# k26_baseboard_cameras.net
KiCad netlist of a schematic drawn in Altium Designer
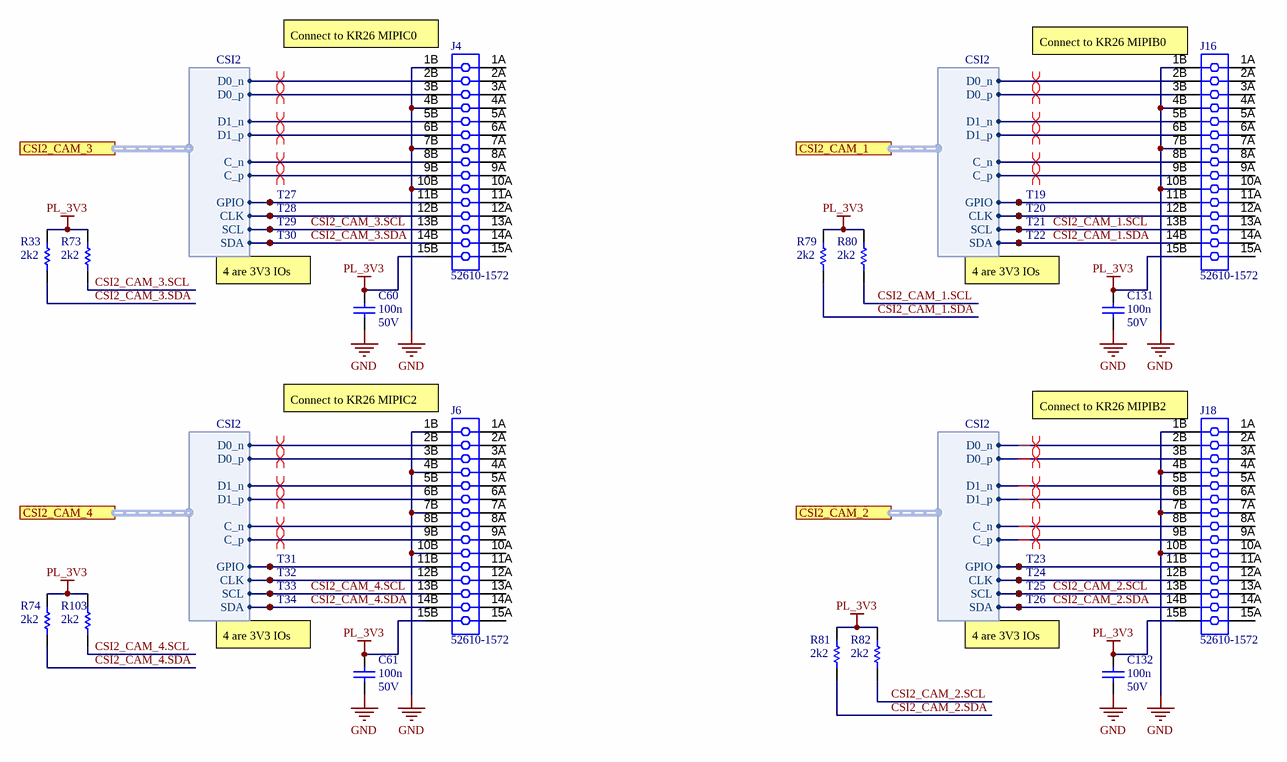
[diagram p0: k26_baseboard_cameras.SchDoc]

(export (version "E")
  (design (tool "Eeschema 10.0.6"))
  (components
    (comp (ref "C60")
      (value "100n")
      (footprint "k26_FPGA_drone_baseboard:CAPC0402")
      (fields
        (field (name "MANUFACTURER") "Yageo")
        (field (name "MANUFACTURER PART NUMBER") "CC0402KRX5R9BB104")
        (field (name "RATED DC VOLTAGE (URDC)") "50V")
      )
      (libsource (lib "k26_FPGA_drone_baseboard") (part "cap0402"))
    )
    (comp (ref "C61")
      (value "100n")
      (footprint "k26_FPGA_drone_baseboard:CAPC0402")
      (fields
        (field (name "MANUFACTURER") "Yageo")
        (field (name "MANUFACTURER PART NUMBER") "CC0402KRX5R9BB104")
        (field (name "RATED DC VOLTAGE (URDC)") "50V")
      )
      (libsource (lib "k26_FPGA_drone_baseboard") (part "cap0402"))
    )
    (comp (ref "C131")
      (value "100n")
      (footprint "k26_FPGA_drone_baseboard:CAPC0402")
      (fields
        (field (name "MANUFACTURER") "Yageo")
        (field (name "MANUFACTURER PART NUMBER") "CC0402KRX5R9BB104")
        (field (name "RATED DC VOLTAGE (URDC)") "50V")
      )
      (libsource (lib "k26_FPGA_drone_baseboard") (part "cap0402"))
    )
    (comp (ref "C132")
      (value "100n")
      (footprint "k26_FPGA_drone_baseboard:CAPC0402")
      (fields
        (field (name "MANUFACTURER") "Yageo")
        (field (name "MANUFACTURER PART NUMBER") "CC0402KRX5R9BB104")
        (field (name "RATED DC VOLTAGE (URDC)") "50V")
      )
      (libsource (lib "k26_FPGA_drone_baseboard") (part "cap0402"))
    )
    (comp (ref "J4")
      (value "52610-1572")
      (footprint "MOLX-52610-1572")
      (fields (field (name "MANUFACTURER") "Molex"))
      (libsource (lib "k26_FPGA_drone_baseboard") (part "MOLX-52610-1572"))
    )
    (comp (ref "J6")
      (value "52610-1572")
      (footprint "MOLX-52610-1572")
      (fields (field (name "MANUFACTURER") "Molex"))
      (libsource (lib "k26_FPGA_drone_baseboard") (part "MOLX-52610-1572"))
    )
    (comp (ref "J16")
      (value "52610-1572")
      (footprint "MOLX-52610-1572")
      (fields (field (name "MANUFACTURER") "Molex"))
      (libsource (lib "k26_FPGA_drone_baseboard") (part "MOLX-52610-1572"))
    )
    (comp (ref "J18")
      (value "52610-1572")
      (footprint "MOLX-52610-1572")
      (fields (field (name "MANUFACTURER") "Molex"))
      (libsource (lib "k26_FPGA_drone_baseboard") (part "MOLX-52610-1572"))
    )
    (comp (ref "R33")
      (value "2k2")
      (footprint "k26_FPGA_drone_baseboard:RES0402")
      (fields
        (field (name "MANUFACTURER") "Vishay")
        (field (name "MANUFACTURER PART NUMBER") "CRCW04022K20FKED")
        (field (name "TOLERANCE") "1%")
      )
      (libsource (lib "k26_FPGA_drone_baseboard") (part "res0402"))
    )
    (comp (ref "R73")
      (value "2k2")
      (footprint "k26_FPGA_drone_baseboard:RES0402")
      (fields
        (field (name "MANUFACTURER") "Vishay")
        (field (name "MANUFACTURER PART NUMBER") "CRCW04022K20FKED")
        (field (name "TOLERANCE") "1%")
      )
      (libsource (lib "k26_FPGA_drone_baseboard") (part "res0402"))
    )
    (comp (ref "R74")
      (value "2k2")
      (footprint "k26_FPGA_drone_baseboard:RES0402")
      (fields
        (field (name "MANUFACTURER") "Vishay")
        (field (name "MANUFACTURER PART NUMBER") "CRCW04022K20FKED")
        (field (name "TOLERANCE") "1%")
      )
      (libsource (lib "k26_FPGA_drone_baseboard") (part "res0402"))
    )
    (comp (ref "R79")
      (value "2k2")
      (footprint "k26_FPGA_drone_baseboard:RES0402")
      (fields
        (field (name "MANUFACTURER") "Vishay")
        (field (name "MANUFACTURER PART NUMBER") "CRCW04022K20FKED")
        (field (name "TOLERANCE") "1%")
      )
      (libsource (lib "k26_FPGA_drone_baseboard") (part "res0402"))
    )
    (comp (ref "R80")
      (value "2k2")
      (footprint "k26_FPGA_drone_baseboard:RES0402")
      (fields
        (field (name "MANUFACTURER") "Vishay")
        (field (name "MANUFACTURER PART NUMBER") "CRCW04022K20FKED")
        (field (name "TOLERANCE") "1%")
      )
      (libsource (lib "k26_FPGA_drone_baseboard") (part "res0402"))
    )
    (comp (ref "R81")
      (value "2k2")
      (footprint "k26_FPGA_drone_baseboard:RES0402")
      (fields
        (field (name "MANUFACTURER") "Vishay")
        (field (name "MANUFACTURER PART NUMBER") "CRCW04022K20FKED")
        (field (name "TOLERANCE") "1%")
      )
      (libsource (lib "k26_FPGA_drone_baseboard") (part "res0402"))
    )
    (comp (ref "R82")
      (value "2k2")
      (footprint "k26_FPGA_drone_baseboard:RES0402")
      (fields
        (field (name "MANUFACTURER") "Vishay")
        (field (name "MANUFACTURER PART NUMBER") "CRCW04022K20FKED")
        (field (name "TOLERANCE") "1%")
      )
      (libsource (lib "k26_FPGA_drone_baseboard") (part "res0402"))
    )
    (comp (ref "R103")
      (value "2k2")
      (footprint "k26_FPGA_drone_baseboard:RES0402")
      (fields
        (field (name "MANUFACTURER") "Vishay")
        (field (name "MANUFACTURER PART NUMBER") "CRCW04022K20FKED")
        (field (name "TOLERANCE") "1%")
      )
      (libsource (lib "k26_FPGA_drone_baseboard") (part "res0402"))
    )
    (comp (ref "T19")
      (value "CMP-01283-1")
      (footprint "Pad-1mm")
      (description "1mm SMT Test Pad")
      (libsource (lib "k26_FPGA_drone_baseboard") (part "CMP-01283-1"))
    )
    (comp (ref "T20")
      (value "CMP-01283-1")
      (footprint "Pad-1mm")
      (description "1mm SMT Test Pad")
      (libsource (lib "k26_FPGA_drone_baseboard") (part "CMP-01283-1"))
    )
    (comp (ref "T21")
      (value "CMP-01283-1")
      (footprint "Pad-1mm")
      (description "1mm SMT Test Pad")
      (libsource (lib "k26_FPGA_drone_baseboard") (part "CMP-01283-1"))
    )
    (comp (ref "T22")
      (value "CMP-01283-1")
      (footprint "Pad-1mm")
      (description "1mm SMT Test Pad")
      (libsource (lib "k26_FPGA_drone_baseboard") (part "CMP-01283-1"))
    )
    (comp (ref "T23")
      (value "CMP-01283-1")
      (footprint "Pad-1mm")
      (description "1mm SMT Test Pad")
      (libsource (lib "k26_FPGA_drone_baseboard") (part "CMP-01283-1"))
    )
    (comp (ref "T24")
      (value "CMP-01283-1")
      (footprint "Pad-1mm")
      (description "1mm SMT Test Pad")
      (libsource (lib "k26_FPGA_drone_baseboard") (part "CMP-01283-1"))
    )
    (comp (ref "T25")
      (value "CMP-01283-1")
      (footprint "Pad-1mm")
      (description "1mm SMT Test Pad")
      (libsource (lib "k26_FPGA_drone_baseboard") (part "CMP-01283-1"))
    )
    (comp (ref "T26")
      (value "CMP-01283-1")
      (footprint "Pad-1mm")
      (description "1mm SMT Test Pad")
      (libsource (lib "k26_FPGA_drone_baseboard") (part "CMP-01283-1"))
    )
    (comp (ref "T27")
      (value "CMP-01283-1")
      (footprint "Pad-1mm")
      (description "1mm SMT Test Pad")
      (libsource (lib "k26_FPGA_drone_baseboard") (part "CMP-01283-1"))
    )
    (comp (ref "T28")
      (value "CMP-01283-1")
      (footprint "Pad-1mm")
      (description "1mm SMT Test Pad")
      (libsource (lib "k26_FPGA_drone_baseboard") (part "CMP-01283-1"))
    )
    (comp (ref "T29")
      (value "CMP-01283-1")
      (footprint "Pad-1mm")
      (description "1mm SMT Test Pad")
      (libsource (lib "k26_FPGA_drone_baseboard") (part "CMP-01283-1"))
    )
    (comp (ref "T30")
      (value "CMP-01283-1")
      (footprint "Pad-1mm")
      (description "1mm SMT Test Pad")
      (libsource (lib "k26_FPGA_drone_baseboard") (part "CMP-01283-1"))
    )
    (comp (ref "T31")
      (value "CMP-01283-1")
      (footprint "Pad-1mm")
      (description "1mm SMT Test Pad")
      (libsource (lib "k26_FPGA_drone_baseboard") (part "CMP-01283-1"))
    )
    (comp (ref "T32")
      (value "CMP-01283-1")
      (footprint "Pad-1mm")
      (description "1mm SMT Test Pad")
      (libsource (lib "k26_FPGA_drone_baseboard") (part "CMP-01283-1"))
    )
    (comp (ref "T33")
      (value "CMP-01283-1")
      (footprint "Pad-1mm")
      (description "1mm SMT Test Pad")
      (libsource (lib "k26_FPGA_drone_baseboard") (part "CMP-01283-1"))
    )
    (comp (ref "T34")
      (value "CMP-01283-1")
      (footprint "Pad-1mm")
      (description "1mm SMT Test Pad")
      (libsource (lib "k26_FPGA_drone_baseboard") (part "CMP-01283-1"))
    )
  )
  (nets
    (net (code "2") (name "/CSI2_CAM_1.SCL") (class "Default")
      (node (ref "J16") (pin "13B") (pinfunction "13B_13B") (pintype "passive"))
      (node (ref "R80") (pin "1") (pinfunction "1_1") (pintype "passive"))
      (node (ref "T21") (pin "1") (pinfunction "1_1") (pintype "passive"))
    )
    (net (code "3") (name "/CSI2_CAM_1.SDA") (class "Default")
      (node (ref "J16") (pin "14B") (pinfunction "14B_14B") (pintype "passive"))
      (node (ref "R79") (pin "1") (pinfunction "1_1") (pintype "passive"))
      (node (ref "T22") (pin "1") (pinfunction "1_1") (pintype "passive"))
    )
    (net (code "4") (name "/CSI2_CAM_2.SCL") (class "Default")
      (node (ref "J18") (pin "13B") (pinfunction "13B_13B") (pintype "passive"))
      (node (ref "R82") (pin "1") (pinfunction "1_1") (pintype "passive"))
      (node (ref "T25") (pin "1") (pinfunction "1_1") (pintype "passive"))
    )
    (net (code "5") (name "/CSI2_CAM_2.SDA") (class "Default")
      (node (ref "J18") (pin "14B") (pinfunction "14B_14B") (pintype "passive"))
      (node (ref "R81") (pin "1") (pinfunction "1_1") (pintype "passive"))
      (node (ref "T26") (pin "1") (pinfunction "1_1") (pintype "passive"))
    )
    (net (code "6") (name "/CSI2_CAM_3.SCL") (class "Default")
      (node (ref "J4") (pin "13B") (pinfunction "13B_13B") (pintype "passive"))
      (node (ref "R73") (pin "1") (pinfunction "1_1") (pintype "passive"))
      (node (ref "T29") (pin "1") (pinfunction "1_1") (pintype "passive"))
    )
    (net (code "7") (name "/CSI2_CAM_3.SDA") (class "Default")
      (node (ref "J4") (pin "14B") (pinfunction "14B_14B") (pintype "passive"))
      (node (ref "R33") (pin "1") (pinfunction "1_1") (pintype "passive"))
      (node (ref "T30") (pin "1") (pinfunction "1_1") (pintype "passive"))
    )
    (net (code "8") (name "/CSI2_CAM_4.SCL") (class "Default")
      (node (ref "J6") (pin "13B") (pinfunction "13B_13B") (pintype "passive"))
      (node (ref "R103") (pin "1") (pinfunction "1_1") (pintype "passive"))
      (node (ref "T33") (pin "1") (pinfunction "1_1") (pintype "passive"))
    )
    (net (code "9") (name "/CSI2_CAM_4.SDA") (class "Default")
      (node (ref "J6") (pin "14B") (pinfunction "14B_14B") (pintype "passive"))
      (node (ref "R74") (pin "1") (pinfunction "1_1") (pintype "passive"))
      (node (ref "T34") (pin "1") (pinfunction "1_1") (pintype "passive"))
    )
    (net (code "11") (name "GND") (class "Default")
      (node (ref "C131") (pin "1") (pinfunction "1_1") (pintype "passive"))
      (node (ref "C132") (pin "1") (pinfunction "1_1") (pintype "passive"))
      (node (ref "C60") (pin "1") (pinfunction "1_1") (pintype "passive"))
      (node (ref "C61") (pin "1") (pinfunction "1_1") (pintype "passive"))
      (node (ref "J16") (pin "10B") (pinfunction "10B_10B") (pintype "passive"))
      (node (ref "J16") (pin "1B") (pinfunction "1B_1B") (pintype "passive"))
      (node (ref "J16") (pin "4B") (pinfunction "4B_4B") (pintype "passive"))
      (node (ref "J16") (pin "7B") (pinfunction "7B_7B") (pintype "passive"))
      (node (ref "J18") (pin "10B") (pinfunction "10B_10B") (pintype "passive"))
      (node (ref "J18") (pin "1B") (pinfunction "1B_1B") (pintype "passive"))
      (node (ref "J18") (pin "4B") (pinfunction "4B_4B") (pintype "passive"))
      (node (ref "J18") (pin "7B") (pinfunction "7B_7B") (pintype "passive"))
      (node (ref "J4") (pin "10B") (pinfunction "10B_10B") (pintype "passive"))
      (node (ref "J4") (pin "1B") (pinfunction "1B_1B") (pintype "passive"))
      (node (ref "J4") (pin "4B") (pinfunction "4B_4B") (pintype "passive"))
      (node (ref "J4") (pin "7B") (pinfunction "7B_7B") (pintype "passive"))
      (node (ref "J6") (pin "10B") (pinfunction "10B_10B") (pintype "passive"))
      (node (ref "J6") (pin "1B") (pinfunction "1B_1B") (pintype "passive"))
      (node (ref "J6") (pin "4B") (pinfunction "4B_4B") (pintype "passive"))
      (node (ref "J6") (pin "7B") (pinfunction "7B_7B") (pintype "passive"))
    )
    (net (code "12") (name "Net-(J4-Pad11B)") (class "Default")
      (node (ref "J4") (pin "11B") (pinfunction "11B_11B") (pintype "passive"))
      (node (ref "T27") (pin "1") (pinfunction "1_1") (pintype "passive"))
    )
    (net (code "13") (name "Net-(J4-Pad12B)") (class "Default")
      (node (ref "J4") (pin "12B") (pinfunction "12B_12B") (pintype "passive"))
      (node (ref "T28") (pin "1") (pinfunction "1_1") (pintype "passive"))
    )
    (net (code "14") (name "Net-(J6-Pad11B)") (class "Default")
      (node (ref "J6") (pin "11B") (pinfunction "11B_11B") (pintype "passive"))
      (node (ref "T31") (pin "1") (pinfunction "1_1") (pintype "passive"))
    )
    (net (code "15") (name "Net-(J6-Pad12B)") (class "Default")
      (node (ref "J6") (pin "12B") (pinfunction "12B_12B") (pintype "passive"))
      (node (ref "T32") (pin "1") (pinfunction "1_1") (pintype "passive"))
    )
    (net (code "16") (name "Net-(J16-Pad11B)") (class "Default")
      (node (ref "J16") (pin "11B") (pinfunction "11B_11B") (pintype "passive"))
      (node (ref "T19") (pin "1") (pinfunction "1_1") (pintype "passive"))
    )
    (net (code "17") (name "Net-(J16-Pad12B)") (class "Default")
      (node (ref "J16") (pin "12B") (pinfunction "12B_12B") (pintype "passive"))
      (node (ref "T20") (pin "1") (pinfunction "1_1") (pintype "passive"))
    )
    (net (code "18") (name "Net-(J18-Pad11B)") (class "Default")
      (node (ref "J18") (pin "11B") (pinfunction "11B_11B") (pintype "passive"))
      (node (ref "T23") (pin "1") (pinfunction "1_1") (pintype "passive"))
    )
    (net (code "19") (name "Net-(J18-Pad12B)") (class "Default")
      (node (ref "J18") (pin "12B") (pinfunction "12B_12B") (pintype "passive"))
      (node (ref "T24") (pin "1") (pinfunction "1_1") (pintype "passive"))
    )
    (net (code "20") (name "PL_3V3") (class "Default")
      (node (ref "C131") (pin "2") (pinfunction "2_2") (pintype "passive"))
      (node (ref "C132") (pin "2") (pinfunction "2_2") (pintype "passive"))
      (node (ref "C60") (pin "2") (pinfunction "2_2") (pintype "passive"))
      (node (ref "C61") (pin "2") (pinfunction "2_2") (pintype "passive"))
      (node (ref "J16") (pin "15B") (pinfunction "15B_15B") (pintype "passive"))
      (node (ref "J18") (pin "15B") (pinfunction "15B_15B") (pintype "passive"))
      (node (ref "J4") (pin "15B") (pinfunction "15B_15B") (pintype "passive"))
      (node (ref "J6") (pin "15B") (pinfunction "15B_15B") (pintype "passive"))
      (node (ref "R103") (pin "2") (pinfunction "2_2") (pintype "passive"))
      (node (ref "R33") (pin "2") (pinfunction "2_2") (pintype "passive"))
      (node (ref "R73") (pin "2") (pinfunction "2_2") (pintype "passive"))
      (node (ref "R74") (pin "2") (pinfunction "2_2") (pintype "passive"))
      (node (ref "R79") (pin "2") (pinfunction "2_2") (pintype "passive"))
      (node (ref "R80") (pin "2") (pinfunction "2_2") (pintype "passive"))
      (node (ref "R81") (pin "2") (pinfunction "2_2") (pintype "passive"))
      (node (ref "R82") (pin "2") (pinfunction "2_2") (pintype "passive"))
    )
    (net (code "21") (name "unconnected-(J4-Pad1A)") (class "Default")
      (node (ref "J4") (pin "1A") (pinfunction "1A_1A") (pintype "passive"))
    )
    (net (code "22") (name "unconnected-(J4-Pad2A)") (class "Default")
      (node (ref "J4") (pin "2A") (pinfunction "2A_2A") (pintype "passive"))
    )
    (net (code "23") (name "unconnected-(J4-Pad2B)") (class "Default")
      (node (ref "J4") (pin "2B") (pinfunction "2B_2B") (pintype "passive"))
    )
    (net (code "24") (name "unconnected-(J4-Pad3A)") (class "Default")
      (node (ref "J4") (pin "3A") (pinfunction "3A_3A") (pintype "passive"))
    )
    (net (code "25") (name "unconnected-(J4-Pad3B)") (class "Default")
      (node (ref "J4") (pin "3B") (pinfunction "3B_3B") (pintype "passive"))
    )
    (net (code "26") (name "unconnected-(J4-Pad4A)") (class "Default")
      (node (ref "J4") (pin "4A") (pinfunction "4A_4A") (pintype "passive"))
    )
    (net (code "27") (name "unconnected-(J4-Pad5A)") (class "Default")
      (node (ref "J4") (pin "5A") (pinfunction "5A_5A") (pintype "passive"))
    )
    (net (code "28") (name "unconnected-(J4-Pad5B)") (class "Default")
      (node (ref "J4") (pin "5B") (pinfunction "5B_5B") (pintype "passive"))
    )
    (net (code "29") (name "unconnected-(J4-Pad6A)") (class "Default")
      (node (ref "J4") (pin "6A") (pinfunction "6A_6A") (pintype "passive"))
    )
    (net (code "30") (name "unconnected-(J4-Pad6B)") (class "Default")
      (node (ref "J4") (pin "6B") (pinfunction "6B_6B") (pintype "passive"))
    )
    (net (code "31") (name "unconnected-(J4-Pad7A)") (class "Default")
      (node (ref "J4") (pin "7A") (pinfunction "7A_7A") (pintype "passive"))
    )
    (net (code "32") (name "unconnected-(J4-Pad8A)") (class "Default")
      (node (ref "J4") (pin "8A") (pinfunction "8A_8A") (pintype "passive"))
    )
    (net (code "33") (name "unconnected-(J4-Pad8B)") (class "Default")
      (node (ref "J4") (pin "8B") (pinfunction "8B_8B") (pintype "passive"))
    )
    (net (code "34") (name "unconnected-(J4-Pad9A)") (class "Default")
      (node (ref "J4") (pin "9A") (pinfunction "9A_9A") (pintype "passive"))
    )
    (net (code "35") (name "unconnected-(J4-Pad9B)") (class "Default")
      (node (ref "J4") (pin "9B") (pinfunction "9B_9B") (pintype "passive"))
    )
    (net (code "36") (name "unconnected-(J4-Pad10A)") (class "Default")
      (node (ref "J4") (pin "10A") (pinfunction "10A_10A") (pintype "passive"))
    )
    (net (code "37") (name "unconnected-(J4-Pad11A)") (class "Default")
      (node (ref "J4") (pin "11A") (pinfunction "11A_11A") (pintype "passive"))
    )
    (net (code "38") (name "unconnected-(J4-Pad12A)") (class "Default")
      (node (ref "J4") (pin "12A") (pinfunction "12A_12A") (pintype "passive"))
    )
    (net (code "39") (name "unconnected-(J4-Pad13A)") (class "Default")
      (node (ref "J4") (pin "13A") (pinfunction "13A_13A") (pintype "passive"))
    )
    (net (code "40") (name "unconnected-(J4-Pad14A)") (class "Default")
      (node (ref "J4") (pin "14A") (pinfunction "14A_14A") (pintype "passive"))
    )
    (net (code "41") (name "unconnected-(J4-Pad15A)") (class "Default")
      (node (ref "J4") (pin "15A") (pinfunction "15A_15A") (pintype "passive"))
    )
    (net (code "42") (name "unconnected-(J6-Pad1A)") (class "Default")
      (node (ref "J6") (pin "1A") (pinfunction "1A_1A") (pintype "passive"))
    )
    (net (code "43") (name "unconnected-(J6-Pad2A)") (class "Default")
      (node (ref "J6") (pin "2A") (pinfunction "2A_2A") (pintype "passive"))
    )
    (net (code "44") (name "unconnected-(J6-Pad2B)") (class "Default")
      (node (ref "J6") (pin "2B") (pinfunction "2B_2B") (pintype "passive"))
    )
    (net (code "45") (name "unconnected-(J6-Pad3A)") (class "Default")
      (node (ref "J6") (pin "3A") (pinfunction "3A_3A") (pintype "passive"))
    )
    (net (code "46") (name "unconnected-(J6-Pad3B)") (class "Default")
      (node (ref "J6") (pin "3B") (pinfunction "3B_3B") (pintype "passive"))
    )
    (net (code "47") (name "unconnected-(J6-Pad4A)") (class "Default")
      (node (ref "J6") (pin "4A") (pinfunction "4A_4A") (pintype "passive"))
    )
    (net (code "48") (name "unconnected-(J6-Pad5A)") (class "Default")
      (node (ref "J6") (pin "5A") (pinfunction "5A_5A") (pintype "passive"))
    )
    (net (code "49") (name "unconnected-(J6-Pad5B)") (class "Default")
      (node (ref "J6") (pin "5B") (pinfunction "5B_5B") (pintype "passive"))
    )
    (net (code "50") (name "unconnected-(J6-Pad6A)") (class "Default")
      (node (ref "J6") (pin "6A") (pinfunction "6A_6A") (pintype "passive"))
    )
    (net (code "51") (name "unconnected-(J6-Pad6B)") (class "Default")
      (node (ref "J6") (pin "6B") (pinfunction "6B_6B") (pintype "passive"))
    )
    (net (code "52") (name "unconnected-(J6-Pad7A)") (class "Default")
      (node (ref "J6") (pin "7A") (pinfunction "7A_7A") (pintype "passive"))
    )
    (net (code "53") (name "unconnected-(J6-Pad8A)") (class "Default")
      (node (ref "J6") (pin "8A") (pinfunction "8A_8A") (pintype "passive"))
    )
    (net (code "54") (name "unconnected-(J6-Pad8B)") (class "Default")
      (node (ref "J6") (pin "8B") (pinfunction "8B_8B") (pintype "passive"))
    )
    (net (code "55") (name "unconnected-(J6-Pad9A)") (class "Default")
      (node (ref "J6") (pin "9A") (pinfunction "9A_9A") (pintype "passive"))
    )
    (net (code "56") (name "unconnected-(J6-Pad9B)") (class "Default")
      (node (ref "J6") (pin "9B") (pinfunction "9B_9B") (pintype "passive"))
    )
    (net (code "57") (name "unconnected-(J6-Pad10A)") (class "Default")
      (node (ref "J6") (pin "10A") (pinfunction "10A_10A") (pintype "passive"))
    )
    (net (code "58") (name "unconnected-(J6-Pad11A)") (class "Default")
      (node (ref "J6") (pin "11A") (pinfunction "11A_11A") (pintype "passive"))
    )
    (net (code "59") (name "unconnected-(J6-Pad12A)") (class "Default")
      (node (ref "J6") (pin "12A") (pinfunction "12A_12A") (pintype "passive"))
    )
    (net (code "60") (name "unconnected-(J6-Pad13A)") (class "Default")
      (node (ref "J6") (pin "13A") (pinfunction "13A_13A") (pintype "passive"))
    )
    (net (code "61") (name "unconnected-(J6-Pad14A)") (class "Default")
      (node (ref "J6") (pin "14A") (pinfunction "14A_14A") (pintype "passive"))
    )
    (net (code "62") (name "unconnected-(J6-Pad15A)") (class "Default")
      (node (ref "J6") (pin "15A") (pinfunction "15A_15A") (pintype "passive"))
    )
    (net (code "63") (name "unconnected-(J16-Pad1A)") (class "Default")
      (node (ref "J16") (pin "1A") (pinfunction "1A_1A") (pintype "passive"))
    )
    (net (code "64") (name "unconnected-(J16-Pad2A)") (class "Default")
      (node (ref "J16") (pin "2A") (pinfunction "2A_2A") (pintype "passive"))
    )
    (net (code "65") (name "unconnected-(J16-Pad2B)") (class "Default")
      (node (ref "J16") (pin "2B") (pinfunction "2B_2B") (pintype "passive"))
    )
    (net (code "66") (name "unconnected-(J16-Pad3A)") (class "Default")
      (node (ref "J16") (pin "3A") (pinfunction "3A_3A") (pintype "passive"))
    )
    (net (code "67") (name "unconnected-(J16-Pad3B)") (class "Default")
      (node (ref "J16") (pin "3B") (pinfunction "3B_3B") (pintype "passive"))
    )
    (net (code "68") (name "unconnected-(J16-Pad4A)") (class "Default")
      (node (ref "J16") (pin "4A") (pinfunction "4A_4A") (pintype "passive"))
    )
    (net (code "69") (name "unconnected-(J16-Pad5A)") (class "Default")
      (node (ref "J16") (pin "5A") (pinfunction "5A_5A") (pintype "passive"))
    )
    (net (code "70") (name "unconnected-(J16-Pad5B)") (class "Default")
      (node (ref "J16") (pin "5B") (pinfunction "5B_5B") (pintype "passive"))
    )
    (net (code "71") (name "unconnected-(J16-Pad6A)") (class "Default")
      (node (ref "J16") (pin "6A") (pinfunction "6A_6A") (pintype "passive"))
    )
    (net (code "72") (name "unconnected-(J16-Pad6B)") (class "Default")
      (node (ref "J16") (pin "6B") (pinfunction "6B_6B") (pintype "passive"))
    )
    (net (code "73") (name "unconnected-(J16-Pad7A)") (class "Default")
      (node (ref "J16") (pin "7A") (pinfunction "7A_7A") (pintype "passive"))
    )
    (net (code "74") (name "unconnected-(J16-Pad8A)") (class "Default")
      (node (ref "J16") (pin "8A") (pinfunction "8A_8A") (pintype "passive"))
    )
    (net (code "75") (name "unconnected-(J16-Pad8B)") (class "Default")
      (node (ref "J16") (pin "8B") (pinfunction "8B_8B") (pintype "passive"))
    )
    (net (code "76") (name "unconnected-(J16-Pad9A)") (class "Default")
      (node (ref "J16") (pin "9A") (pinfunction "9A_9A") (pintype "passive"))
    )
    (net (code "77") (name "unconnected-(J16-Pad9B)") (class "Default")
      (node (ref "J16") (pin "9B") (pinfunction "9B_9B") (pintype "passive"))
    )
    (net (code "78") (name "unconnected-(J16-Pad10A)") (class "Default")
      (node (ref "J16") (pin "10A") (pinfunction "10A_10A") (pintype "passive"))
    )
    (net (code "79") (name "unconnected-(J16-Pad11A)") (class "Default")
      (node (ref "J16") (pin "11A") (pinfunction "11A_11A") (pintype "passive"))
    )
    (net (code "80") (name "unconnected-(J16-Pad12A)") (class "Default")
      (node (ref "J16") (pin "12A") (pinfunction "12A_12A") (pintype "passive"))
    )
    (net (code "81") (name "unconnected-(J16-Pad13A)") (class "Default")
      (node (ref "J16") (pin "13A") (pinfunction "13A_13A") (pintype "passive"))
    )
    (net (code "82") (name "unconnected-(J16-Pad14A)") (class "Default")
      (node (ref "J16") (pin "14A") (pinfunction "14A_14A") (pintype "passive"))
    )
    (net (code "83") (name "unconnected-(J16-Pad15A)") (class "Default")
      (node (ref "J16") (pin "15A") (pinfunction "15A_15A") (pintype "passive"))
    )
    (net (code "84") (name "unconnected-(J18-Pad1A)") (class "Default")
      (node (ref "J18") (pin "1A") (pinfunction "1A_1A") (pintype "passive"))
    )
    (net (code "85") (name "unconnected-(J18-Pad2A)") (class "Default")
      (node (ref "J18") (pin "2A") (pinfunction "2A_2A") (pintype "passive"))
    )
    (net (code "86") (name "unconnected-(J18-Pad2B)") (class "Default")
      (node (ref "J18") (pin "2B") (pinfunction "2B_2B") (pintype "passive"))
    )
    (net (code "87") (name "unconnected-(J18-Pad3A)") (class "Default")
      (node (ref "J18") (pin "3A") (pinfunction "3A_3A") (pintype "passive"))
    )
    (net (code "88") (name "unconnected-(J18-Pad3B)") (class "Default")
      (node (ref "J18") (pin "3B") (pinfunction "3B_3B") (pintype "passive"))
    )
    (net (code "89") (name "unconnected-(J18-Pad4A)") (class "Default")
      (node (ref "J18") (pin "4A") (pinfunction "4A_4A") (pintype "passive"))
    )
    (net (code "90") (name "unconnected-(J18-Pad5A)") (class "Default")
      (node (ref "J18") (pin "5A") (pinfunction "5A_5A") (pintype "passive"))
    )
    (net (code "91") (name "unconnected-(J18-Pad5B)") (class "Default")
      (node (ref "J18") (pin "5B") (pinfunction "5B_5B") (pintype "passive"))
    )
    (net (code "92") (name "unconnected-(J18-Pad6A)") (class "Default")
      (node (ref "J18") (pin "6A") (pinfunction "6A_6A") (pintype "passive"))
    )
    (net (code "93") (name "unconnected-(J18-Pad6B)") (class "Default")
      (node (ref "J18") (pin "6B") (pinfunction "6B_6B") (pintype "passive"))
    )
    (net (code "94") (name "unconnected-(J18-Pad7A)") (class "Default")
      (node (ref "J18") (pin "7A") (pinfunction "7A_7A") (pintype "passive"))
    )
    (net (code "95") (name "unconnected-(J18-Pad8A)") (class "Default")
      (node (ref "J18") (pin "8A") (pinfunction "8A_8A") (pintype "passive"))
    )
    (net (code "96") (name "unconnected-(J18-Pad8B)") (class "Default")
      (node (ref "J18") (pin "8B") (pinfunction "8B_8B") (pintype "passive"))
    )
    (net (code "97") (name "unconnected-(J18-Pad9A)") (class "Default")
      (node (ref "J18") (pin "9A") (pinfunction "9A_9A") (pintype "passive"))
    )
    (net (code "98") (name "unconnected-(J18-Pad9B)") (class "Default")
      (node (ref "J18") (pin "9B") (pinfunction "9B_9B") (pintype "passive"))
    )
    (net (code "99") (name "unconnected-(J18-Pad10A)") (class "Default")
      (node (ref "J18") (pin "10A") (pinfunction "10A_10A") (pintype "passive"))
    )
    (net (code "100") (name "unconnected-(J18-Pad11A)") (class "Default")
      (node (ref "J18") (pin "11A") (pinfunction "11A_11A") (pintype "passive"))
    )
    (net (code "101") (name "unconnected-(J18-Pad12A)") (class "Default")
      (node (ref "J18") (pin "12A") (pinfunction "12A_12A") (pintype "passive"))
    )
    (net (code "102") (name "unconnected-(J18-Pad13A)") (class "Default")
      (node (ref "J18") (pin "13A") (pinfunction "13A_13A") (pintype "passive"))
    )
    (net (code "103") (name "unconnected-(J18-Pad14A)") (class "Default")
      (node (ref "J18") (pin "14A") (pinfunction "14A_14A") (pintype "passive"))
    )
    (net (code "104") (name "unconnected-(J18-Pad15A)") (class "Default")
      (node (ref "J18") (pin "15A") (pinfunction "15A_15A") (pintype "passive"))
    )
  )
)
